# try1.net
KiCad netlist of a schematic drawn in EAGLE
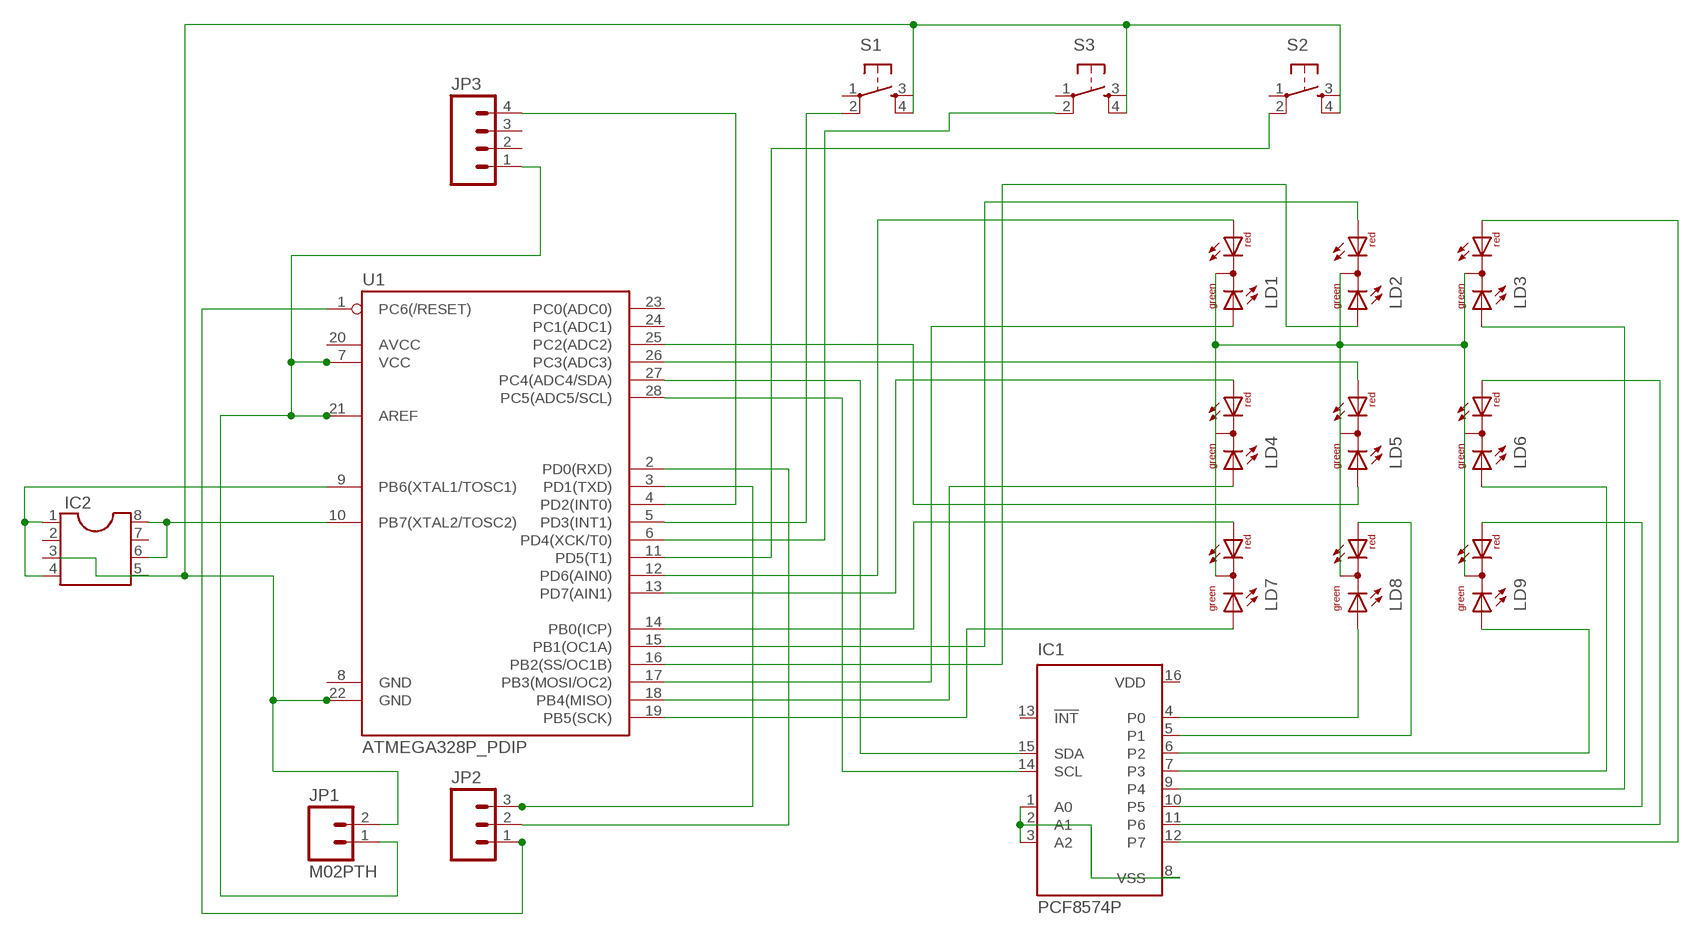
[diagram p0: schematic, sheet 1]

(export (version "E")
  (design (tool "Eeschema 10.0.6"))
  (components
    (comp (ref "IC1")
      (value "PCF8574P")
      (footprint "eagle-import:DIL16")
      (fields (field (name "MPN") "PCF8574PN"))
      (libsource (lib "eagle-import") (part "PCF8574P"))
    )
    (comp (ref "IC2")
      (value "DIL8S")
      (footprint "eagle-import:SOCKET-08")
      (libsource (lib "eagle-import") (part "DIL8S"))
    )
    (comp (ref "JP1")
      (value "M02PTH")
      (footprint "eagle-import:1X02")
      (libsource (lib "eagle-import") (part "M02PTH"))
    )
    (comp (ref "JP2")
      (value "M03PTH")
      (footprint "eagle-import:1X03")
      (libsource (lib "eagle-import") (part "M03PTH"))
    )
    (comp (ref "JP3")
      (value "M04PTH")
      (footprint "eagle-import:1X04")
      (libsource (lib "eagle-import") (part "M04PTH"))
    )
    (comp (ref "LD1")
      (value "DUOLED-RG-C")
      (footprint "eagle-import:DUOLED-C-5MM")
      (libsource (lib "eagle-import") (part "DUOLED-RG-C"))
    )
    (comp (ref "LD2")
      (value "DUOLED-RG-C")
      (footprint "eagle-import:DUOLED-C-5MM")
      (libsource (lib "eagle-import") (part "DUOLED-RG-C"))
    )
    (comp (ref "LD3")
      (value "DUOLED-RG-C")
      (footprint "eagle-import:DUOLED-C-5MM")
      (libsource (lib "eagle-import") (part "DUOLED-RG-C"))
    )
    (comp (ref "LD4")
      (value "DUOLED-RG-C")
      (footprint "eagle-import:DUOLED-C-5MM")
      (libsource (lib "eagle-import") (part "DUOLED-RG-C"))
    )
    (comp (ref "LD5")
      (value "DUOLED-RG-C")
      (footprint "eagle-import:DUOLED-C-5MM")
      (libsource (lib "eagle-import") (part "DUOLED-RG-C"))
    )
    (comp (ref "LD6")
      (value "DUOLED-RG-C")
      (footprint "eagle-import:DUOLED-C-5MM")
      (libsource (lib "eagle-import") (part "DUOLED-RG-C"))
    )
    (comp (ref "LD7")
      (value "DUOLED-RG-C")
      (footprint "eagle-import:DUOLED-C-5MM")
      (libsource (lib "eagle-import") (part "DUOLED-RG-C"))
    )
    (comp (ref "LD8")
      (value "DUOLED-RG-C")
      (footprint "eagle-import:DUOLED-C-5MM")
      (libsource (lib "eagle-import") (part "DUOLED-RG-C"))
    )
    (comp (ref "LD9")
      (value "DUOLED-RG-C")
      (footprint "eagle-import:DUOLED-C-5MM")
      (libsource (lib "eagle-import") (part "DUOLED-RG-C"))
    )
    (comp (ref "S1")
      (value "TAC_SWITCHPTH")
      (footprint "eagle-import:TACTILE-PTH")
      (libsource (lib "eagle-import") (part "TAC_SWITCHPTH"))
    )
    (comp (ref "S2")
      (value "TAC_SWITCHPTH")
      (footprint "eagle-import:TACTILE-PTH")
      (libsource (lib "eagle-import") (part "TAC_SWITCHPTH"))
    )
    (comp (ref "S3")
      (value "TAC_SWITCHPTH")
      (footprint "eagle-import:TACTILE-PTH")
      (libsource (lib "eagle-import") (part "TAC_SWITCHPTH"))
    )
    (comp (ref "U1")
      (value "ATMEGA328P_PDIP")
      (footprint "eagle-import:DIL28-3")
      (libsource (lib "eagle-import") (part "ATMEGA328P_PDIP"))
    )
  )
  (nets
    (net (code "1") (name "/VCC") (class "Default")
      (node (ref "JP1") (pin "1") (pinfunction "1_1") (pintype "passive"))
      (node (ref "JP3") (pin "1") (pinfunction "1_1") (pintype "passive"))
      (node (ref "LD1") (pin "C") (pinfunction "C_C") (pintype "passive"))
      (node (ref "LD2") (pin "C") (pinfunction "C_C") (pintype "passive"))
      (node (ref "LD3") (pin "C") (pinfunction "C_C") (pintype "passive"))
      (node (ref "LD7") (pin "C") (pinfunction "C_C") (pintype "passive"))
      (node (ref "LD8") (pin "C") (pinfunction "C_C") (pintype "passive"))
      (node (ref "LD9") (pin "C") (pinfunction "C_C") (pintype "passive"))
      (node (ref "U1") (pin "21") (pinfunction "AREF_21") (pintype "bidirectional"))
      (node (ref "U1") (pin "7") (pinfunction "VCC_7") (pintype "bidirectional"))
    )
    (net (code "2") (name "/VDD") (class "Default")
      (node (ref "IC1") (pin "16") (pinfunction "VDD_16") (pintype "power_in"))
    )
    (net (code "3") (name "Net-(IC1-A0)") (class "Default")
      (node (ref "IC1") (pin "1") (pinfunction "A0_1") (pintype "input"))
      (node (ref "IC1") (pin "2") (pinfunction "A1_2") (pintype "input"))
      (node (ref "IC1") (pin "3") (pinfunction "A2_3") (pintype "input"))
      (node (ref "IC1") (pin "8") (pinfunction "VSS_8") (pintype "power_in"))
    )
    (net (code "4") (name "Net-(IC1-P0)") (class "Default")
      (node (ref "IC1") (pin "4") (pinfunction "P0_4") (pintype "bidirectional"))
      (node (ref "LD8") (pin "AX") (pinfunction "AG_AX") (pintype "passive"))
    )
    (net (code "5") (name "Net-(IC1-P1)") (class "Default")
      (node (ref "IC1") (pin "5") (pinfunction "P1_5") (pintype "bidirectional"))
      (node (ref "LD8") (pin "AR") (pinfunction "AR_AR") (pintype "passive"))
    )
    (net (code "6") (name "Net-(IC1-P2)") (class "Default")
      (node (ref "IC1") (pin "6") (pinfunction "P2_6") (pintype "bidirectional"))
      (node (ref "LD9") (pin "AX") (pinfunction "AG_AX") (pintype "passive"))
    )
    (net (code "7") (name "Net-(IC1-P3)") (class "Default")
      (node (ref "IC1") (pin "7") (pinfunction "P3_7") (pintype "bidirectional"))
      (node (ref "LD6") (pin "AX") (pinfunction "AG_AX") (pintype "passive"))
    )
    (net (code "8") (name "Net-(IC1-P4)") (class "Default")
      (node (ref "IC1") (pin "9") (pinfunction "P4_9") (pintype "bidirectional"))
      (node (ref "LD3") (pin "AX") (pinfunction "AG_AX") (pintype "passive"))
    )
    (net (code "9") (name "Net-(IC1-P5)") (class "Default")
      (node (ref "IC1") (pin "10") (pinfunction "P5_10") (pintype "bidirectional"))
      (node (ref "LD9") (pin "AR") (pinfunction "AR_AR") (pintype "passive"))
    )
    (net (code "10") (name "Net-(IC1-P6)") (class "Default")
      (node (ref "IC1") (pin "11") (pinfunction "P6_11") (pintype "bidirectional"))
      (node (ref "LD6") (pin "AR") (pinfunction "AR_AR") (pintype "passive"))
    )
    (net (code "11") (name "Net-(IC1-P7)") (class "Default")
      (node (ref "IC1") (pin "12") (pinfunction "P7_12") (pintype "bidirectional"))
      (node (ref "LD3") (pin "AR") (pinfunction "AR_AR") (pintype "passive"))
    )
    (net (code "12") (name "Net-(IC1-SCL)") (class "Default")
      (node (ref "IC1") (pin "14") (pinfunction "SCL_14") (pintype "input"))
      (node (ref "U1") (pin "28") (pinfunction "PC5(ADC5/SCL)_28") (pintype "bidirectional"))
    )
    (net (code "13") (name "Net-(IC1-SDA)") (class "Default")
      (node (ref "IC1") (pin "15") (pinfunction "SDA_15") (pintype "bidirectional"))
      (node (ref "U1") (pin "27") (pinfunction "PC4(ADC4/SDA)_27") (pintype "bidirectional"))
    )
    (net (code "14") (name "Net-(JP1-Pad2)") (class "Default")
      (node (ref "JP1") (pin "2") (pinfunction "2_2") (pintype "passive"))
      (node (ref "S1") (pin "4") (pinfunction "4_4") (pintype "passive"))
      (node (ref "S2") (pin "4") (pinfunction "4_4") (pintype "passive"))
      (node (ref "S3") (pin "4") (pinfunction "4_4") (pintype "passive"))
      (node (ref "U1") (pin "22") (pinfunction "GND_22") (pintype "bidirectional"))
    )
    (net (code "15") (name "Net-(LD1-AG)") (class "Default")
      (node (ref "LD1") (pin "AX") (pinfunction "AG_AX") (pintype "passive"))
      (node (ref "U1") (pin "17") (pinfunction "PB3(MOSI/OC2)_17") (pintype "bidirectional"))
    )
    (net (code "16") (name "Net-(LD2-AG)") (class "Default")
      (node (ref "LD2") (pin "AX") (pinfunction "AG_AX") (pintype "passive"))
      (node (ref "U1") (pin "16") (pinfunction "PB2(SS/OC1B)_16") (pintype "bidirectional"))
    )
    (net (code "17") (name "Net-(LD4-AG)") (class "Default")
      (node (ref "LD4") (pin "AX") (pinfunction "AG_AX") (pintype "passive"))
      (node (ref "U1") (pin "18") (pinfunction "PB4(MISO)_18") (pintype "bidirectional"))
    )
    (net (code "18") (name "Net-(LD5-AG)") (class "Default")
      (node (ref "LD5") (pin "AX") (pinfunction "AG_AX") (pintype "passive"))
      (node (ref "U1") (pin "25") (pinfunction "PC2(ADC2)_25") (pintype "bidirectional"))
    )
    (net (code "19") (name "Net-(LD7-AG)") (class "Default")
      (node (ref "LD7") (pin "AX") (pinfunction "AG_AX") (pintype "passive"))
      (node (ref "U1") (pin "19") (pinfunction "PB5(SCK)_19") (pintype "bidirectional"))
    )
    (net (code "20") (name "Net-(U1-PB0(ICP))") (class "Default")
      (node (ref "LD7") (pin "AR") (pinfunction "AR_AR") (pintype "passive"))
      (node (ref "U1") (pin "14") (pinfunction "PB0(ICP)_14") (pintype "bidirectional"))
    )
    (net (code "21") (name "Net-(U1-PB1(OC1A))") (class "Default")
      (node (ref "LD2") (pin "AR") (pinfunction "AR_AR") (pintype "passive"))
      (node (ref "U1") (pin "15") (pinfunction "PB1(OC1A)_15") (pintype "bidirectional"))
    )
    (net (code "22") (name "Net-(U1-PB6(XTAL1{slash}TOSC1))") (class "Default")
      (node (ref "IC2") (pin "1") (pinfunction "1_1") (pintype "passive"))
      (node (ref "IC2") (pin "4") (pinfunction "4_4") (pintype "passive"))
      (node (ref "U1") (pin "9") (pinfunction "PB6(XTAL1/TOSC1)_9") (pintype "bidirectional"))
    )
    (net (code "23") (name "Net-(U1-PB7(XTAL2{slash}TOSC2))") (class "Default")
      (node (ref "IC2") (pin "6") (pinfunction "6_6") (pintype "passive"))
      (node (ref "IC2") (pin "8") (pinfunction "8_8") (pintype "passive"))
      (node (ref "U1") (pin "10") (pinfunction "PB7(XTAL2/TOSC2)_10") (pintype "bidirectional"))
    )
    (net (code "24") (name "Net-(U1-PC3(ADC3))") (class "Default")
      (node (ref "LD5") (pin "AR") (pinfunction "AR_AR") (pintype "passive"))
      (node (ref "U1") (pin "26") (pinfunction "PC3(ADC3)_26") (pintype "bidirectional"))
    )
    (net (code "25") (name "Net-(U1-PC6({slash}RESET))") (class "Default")
      (node (ref "JP2") (pin "1") (pinfunction "1_1") (pintype "passive"))
      (node (ref "U1") (pin "1") (pinfunction "PC6(/RESET)_1") (pintype "bidirectional"))
    )
    (net (code "26") (name "Net-(U1-PD0(RXD))") (class "Default")
      (node (ref "JP2") (pin "2") (pinfunction "2_2") (pintype "passive"))
      (node (ref "U1") (pin "2") (pinfunction "PD0(RXD)_2") (pintype "bidirectional"))
    )
    (net (code "27") (name "Net-(U1-PD1(TXD))") (class "Default")
      (node (ref "JP2") (pin "3") (pinfunction "3_3") (pintype "passive"))
      (node (ref "U1") (pin "3") (pinfunction "PD1(TXD)_3") (pintype "bidirectional"))
    )
    (net (code "28") (name "Net-(U1-PD2(INT0))") (class "Default")
      (node (ref "JP3") (pin "4") (pinfunction "4_4") (pintype "passive"))
      (node (ref "U1") (pin "4") (pinfunction "PD2(INT0)_4") (pintype "bidirectional"))
    )
    (net (code "29") (name "Net-(U1-PD3(INT1))") (class "Default")
      (node (ref "S1") (pin "2") (pinfunction "2_2") (pintype "passive"))
      (node (ref "U1") (pin "5") (pinfunction "PD3(INT1)_5") (pintype "bidirectional"))
    )
    (net (code "30") (name "Net-(U1-PD4(XCK{slash}T0))") (class "Default")
      (node (ref "S3") (pin "2") (pinfunction "2_2") (pintype "passive"))
      (node (ref "U1") (pin "6") (pinfunction "PD4(XCK/T0)_6") (pintype "bidirectional"))
    )
    (net (code "31") (name "Net-(U1-PD5(T1))") (class "Default")
      (node (ref "S2") (pin "2") (pinfunction "2_2") (pintype "passive"))
      (node (ref "U1") (pin "11") (pinfunction "PD5(T1)_11") (pintype "bidirectional"))
    )
    (net (code "32") (name "Net-(U1-PD6(AIN0))") (class "Default")
      (node (ref "LD1") (pin "AR") (pinfunction "AR_AR") (pintype "passive"))
      (node (ref "U1") (pin "12") (pinfunction "PD6(AIN0)_12") (pintype "bidirectional"))
    )
    (net (code "33") (name "Net-(U1-PD7(AIN1))") (class "Default")
      (node (ref "LD4") (pin "AR") (pinfunction "AR_AR") (pintype "passive"))
      (node (ref "U1") (pin "13") (pinfunction "PD7(AIN1)_13") (pintype "bidirectional"))
    )
    (net (code "34") (name "unconnected-(IC1-~{INT}-Pad13)") (class "Default")
      (node (ref "IC1") (pin "13") (pinfunction "~{INT}_13") (pintype "output"))
    )
    (net (code "35") (name "unconnected-(IC2-Pad2)") (class "Default")
      (node (ref "IC2") (pin "2") (pinfunction "2_2") (pintype "passive"))
    )
    (net (code "36") (name "unconnected-(IC2-Pad3)") (class "Default")
      (node (ref "IC2") (pin "3") (pinfunction "3_3") (pintype "passive"))
    )
    (net (code "37") (name "unconnected-(IC2-Pad5)") (class "Default")
      (node (ref "IC2") (pin "5") (pinfunction "5_5") (pintype "passive"))
    )
    (net (code "38") (name "unconnected-(IC2-Pad7)") (class "Default")
      (node (ref "IC2") (pin "7") (pinfunction "7_7") (pintype "passive"))
    )
    (net (code "39") (name "unconnected-(JP3-Pad2)") (class "Default")
      (node (ref "JP3") (pin "2") (pinfunction "2_2") (pintype "passive"))
    )
    (net (code "40") (name "unconnected-(JP3-Pad3)") (class "Default")
      (node (ref "JP3") (pin "3") (pinfunction "3_3") (pintype "passive"))
    )
    (net (code "41") (name "unconnected-(LD4-PadC)") (class "Default")
      (node (ref "LD4") (pin "C") (pinfunction "C_C") (pintype "passive"))
    )
    (net (code "42") (name "unconnected-(LD5-PadC)") (class "Default")
      (node (ref "LD5") (pin "C") (pinfunction "C_C") (pintype "passive"))
    )
    (net (code "43") (name "unconnected-(LD6-PadC)") (class "Default")
      (node (ref "LD6") (pin "C") (pinfunction "C_C") (pintype "passive"))
    )
    (net (code "44") (name "unconnected-(S1-Pad1)") (class "Default")
      (node (ref "S1") (pin "1") (pinfunction "1_1") (pintype "passive"))
    )
    (net (code "45") (name "unconnected-(S1-Pad3)") (class "Default")
      (node (ref "S1") (pin "3") (pinfunction "3_3") (pintype "passive"))
    )
    (net (code "46") (name "unconnected-(S2-Pad1)") (class "Default")
      (node (ref "S2") (pin "1") (pinfunction "1_1") (pintype "passive"))
    )
    (net (code "47") (name "unconnected-(S2-Pad3)") (class "Default")
      (node (ref "S2") (pin "3") (pinfunction "3_3") (pintype "passive"))
    )
    (net (code "48") (name "unconnected-(S3-Pad1)") (class "Default")
      (node (ref "S3") (pin "1") (pinfunction "1_1") (pintype "passive"))
    )
    (net (code "49") (name "unconnected-(S3-Pad3)") (class "Default")
      (node (ref "S3") (pin "3") (pinfunction "3_3") (pintype "passive"))
    )
    (net (code "50") (name "unconnected-(U1-AVCC-Pad20)") (class "Default")
      (node (ref "U1") (pin "20") (pinfunction "AVCC_20") (pintype "bidirectional"))
    )
    (net (code "51") (name "unconnected-(U1-GND-Pad8)") (class "Default")
      (node (ref "U1") (pin "8") (pinfunction "GND_8") (pintype "bidirectional"))
    )
    (net (code "52") (name "unconnected-(U1-PC0(ADC0)-Pad23)") (class "Default")
      (node (ref "U1") (pin "23") (pinfunction "PC0(ADC0)_23") (pintype "bidirectional"))
    )
    (net (code "53") (name "unconnected-(U1-PC1(ADC1)-Pad24)") (class "Default")
      (node (ref "U1") (pin "24") (pinfunction "PC1(ADC1)_24") (pintype "bidirectional"))
    )
  )
)
